# 555.net
KiCad netlist of a schematic drawn in EAGLE
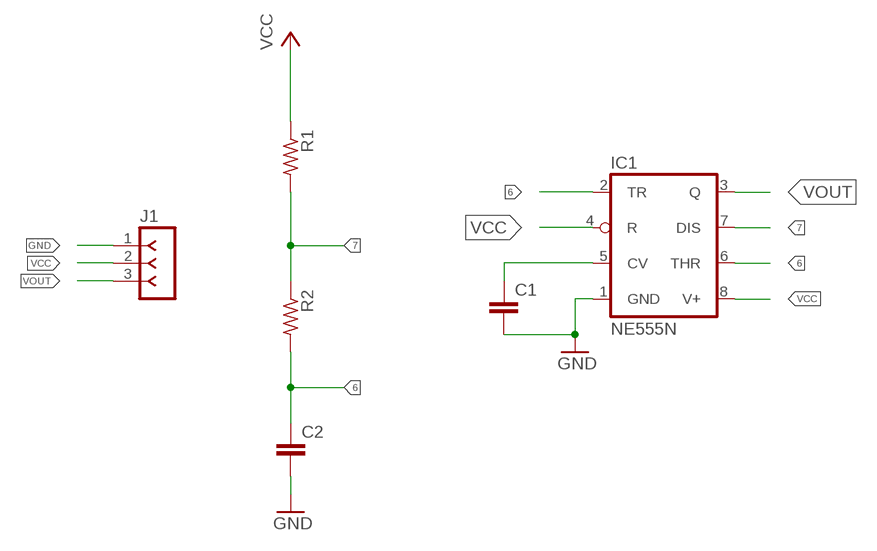
[diagram p0: schematic, sheet 1]

(export (version "E")
  (design (tool "Eeschema 10.0.6"))
  (components
    (comp (ref "C1")
      (value "C2.5/2")
      (footprint "eagle-import:C2.5-2")
      (libsource (lib "eagle-import") (part "C2.5/2"))
    )
    (comp (ref "C2")
      (value "C2.5/2")
      (footprint "eagle-import:C2.5-2")
      (libsource (lib "eagle-import") (part "C2.5/2"))
    )
    (comp (ref "IC1")
      (value "NE555N")
      (footprint "eagle-import:DIL08-ROUND")
      (libsource (lib "eagle-import") (part "555NNE"))
    )
    (comp (ref "J1")
      (value "F-1X03-SIP-100-40")
      (footprint "eagle-import:SIP-100-03-40")
      (libsource (lib "eagle-import") (part "F-1X03-SIP-100-40"))
    )
    (comp (ref "R1")
      (value "R-US_0204/7")
      (footprint "eagle-import:0204_7")
      (libsource (lib "eagle-import") (part "R-US_0204/7"))
    )
    (comp (ref "R2")
      (value "R-US_0204/7")
      (footprint "eagle-import:0204_7")
      (libsource (lib "eagle-import") (part "R-US_0204/7"))
    )
  )
  (nets
    (net (code "1") (name "6") (class "Default")
      (node (ref "C2") (pin "1") (pinfunction "1_1") (pintype "passive"))
      (node (ref "IC1") (pin "2") (pinfunction "TR_2") (pintype "input"))
      (node (ref "IC1") (pin "6") (pinfunction "THR_6") (pintype "input"))
      (node (ref "R2") (pin "2") (pinfunction "2_2") (pintype "passive"))
    )
    (net (code "2") (name "7") (class "Default")
      (node (ref "IC1") (pin "7") (pinfunction "DIS_7") (pintype "input"))
      (node (ref "R1") (pin "2") (pinfunction "2_2") (pintype "passive"))
      (node (ref "R2") (pin "1") (pinfunction "1_1") (pintype "passive"))
    )
    (net (code "3") (name "GND") (class "Default")
      (node (ref "C1") (pin "2") (pinfunction "2_2") (pintype "passive"))
      (node (ref "C2") (pin "2") (pinfunction "2_2") (pintype "passive"))
      (node (ref "IC1") (pin "1") (pinfunction "GND_1") (pintype "power_in"))
      (node (ref "J1") (pin "1") (pinfunction "1_1") (pintype "passive"))
    )
    (net (code "4") (name "Net-(IC1-CV)") (class "Default")
      (node (ref "C1") (pin "1") (pinfunction "1_1") (pintype "passive"))
      (node (ref "IC1") (pin "5") (pinfunction "CV_5") (pintype "input"))
    )
    (net (code "5") (name "VCC") (class "Default")
      (node (ref "IC1") (pin "4") (pinfunction "R_4") (pintype "input"))
      (node (ref "IC1") (pin "8") (pinfunction "V+_8") (pintype "power_in"))
      (node (ref "J1") (pin "2") (pinfunction "2_2") (pintype "passive"))
      (node (ref "R1") (pin "1") (pinfunction "1_1") (pintype "passive"))
    )
    (net (code "6") (name "VOUT") (class "Default")
      (node (ref "IC1") (pin "3") (pinfunction "Q_3") (pintype "output"))
      (node (ref "J1") (pin "3") (pinfunction "3_3") (pintype "passive"))
    )
  )
)
